# node-mcu-pack-single-sided.net
KiCad netlist of a schematic drawn in EAGLE
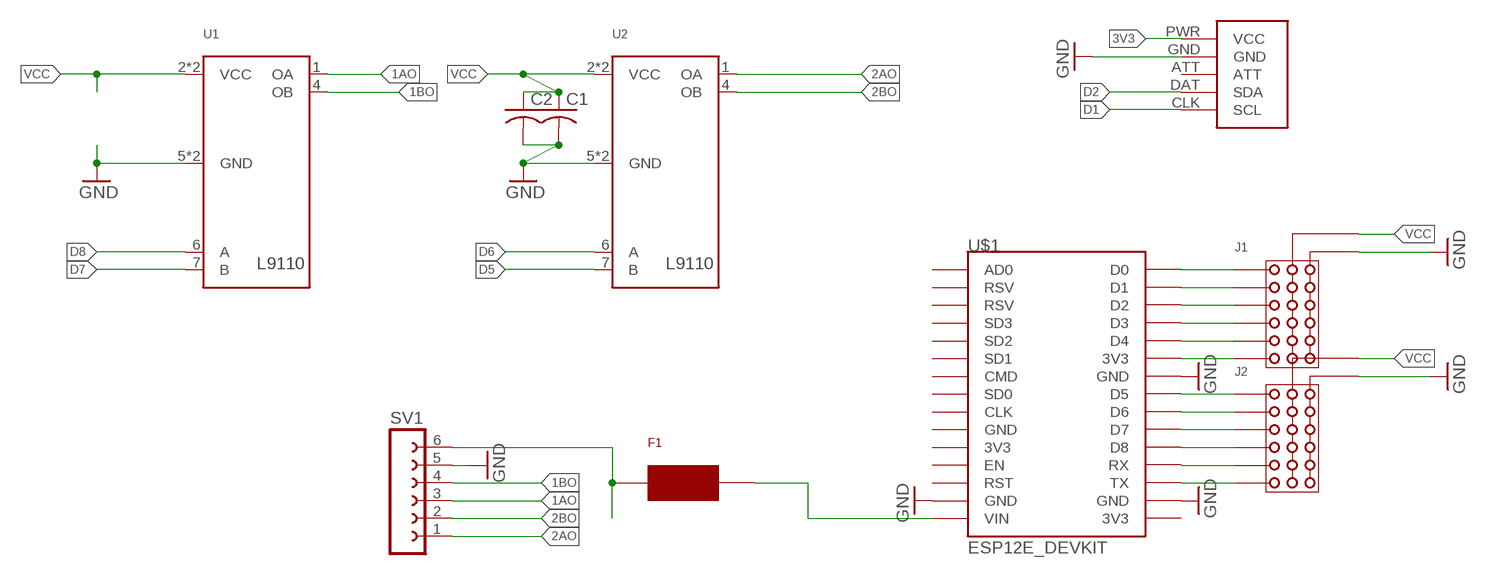
[diagram p0: schematic, sheet 1]

(export (version "E")
  (design (tool "Eeschema 10.0.6"))
  (components
    (comp (ref "C1")
      (value "C-USC0805")
      (footprint "eagle-import:C0805")
      (libsource (lib "eagle-import") (part "C-USC0805"))
    )
    (comp (ref "C2")
      (value "C-USC0805")
      (footprint "eagle-import:C0805")
      (libsource (lib "eagle-import") (part "C-USC0805"))
    )
    (comp (ref "F1")
      (value "0154")
      (footprint "eagle-import:0154")
      (libsource (lib "eagle-import") (part "0154"))
    )
    (comp (ref "J1")
      (value "IOBLOCK6")
      (footprint "eagle-import:IOBLOCK100MILX6")
      (libsource (lib "eagle-import") (part "IOBLOCK6"))
    )
    (comp (ref "J2")
      (value "IOBLOCK6")
      (footprint "eagle-import:IOBLOCK100MILX6")
      (libsource (lib "eagle-import") (part "IOBLOCK6"))
    )
    (comp (ref "SV1")
      (value "FE06-1")
      (footprint "eagle-import:FE06")
      (libsource (lib "eagle-import") (part "FE06-1"))
    )
    (comp (ref "U$1")
      (value "ESP12E_DEVKIT")
      (footprint "eagle-import:ESP12E_DEVKIT")
      (libsource (lib "eagle-import") (part "ESP12E_DEVKIT"))
    )
    (comp (ref "U$2")
      (value "WIICHUCKOUTIE")
      (footprint "eagle-import:CHUCK-OUTIE")
      (libsource (lib "eagle-import") (part "WIICHUCKOUTIE"))
    )
    (comp (ref "U1")
      (value "L9110SMT")
      (footprint "eagle-import:8S1")
      (libsource (lib "eagle-import") (part "L9110SMT"))
    )
    (comp (ref "U2")
      (value "L9110SMT")
      (footprint "eagle-import:8S1")
      (libsource (lib "eagle-import") (part "L9110SMT"))
    )
  )
  (nets
    (net (code "1") (name "1AO") (class "Default")
      (node (ref "SV1") (pin "3") (pinfunction "3_3") (pintype "passive"))
      (node (ref "U1") (pin "1") (pinfunction "OA_1") (pintype "bidirectional"))
    )
    (net (code "2") (name "1BO") (class "Default")
      (node (ref "SV1") (pin "4") (pinfunction "4_4") (pintype "passive"))
      (node (ref "U1") (pin "4") (pinfunction "OB_4") (pintype "bidirectional"))
    )
    (net (code "3") (name "2AO") (class "Default")
      (node (ref "SV1") (pin "1") (pinfunction "1_1") (pintype "passive"))
      (node (ref "U2") (pin "1") (pinfunction "OA_1") (pintype "bidirectional"))
    )
    (net (code "4") (name "2BO") (class "Default")
      (node (ref "SV1") (pin "2") (pinfunction "2_2") (pintype "passive"))
      (node (ref "U2") (pin "4") (pinfunction "OB_4") (pintype "bidirectional"))
    )
    (net (code "5") (name "3V3") (class "Default")
      (node (ref "J1") (pin "P$6") (pinfunction "P$6_P$6") (pintype "bidirectional"))
      (node (ref "U$1") (pin "3V3@1") (pinfunction "3V3_3V3@1") (pintype "bidirectional"))
      (node (ref "U$2") (pin "PWR") (pinfunction "VCC_PWR") (pintype "bidirectional"))
    )
    (net (code "6") (name "D1") (class "Default")
      (node (ref "J1") (pin "P$2") (pinfunction "P$2_P$2") (pintype "bidirectional"))
      (node (ref "U$1") (pin "D1") (pinfunction "D1_D1") (pintype "bidirectional"))
      (node (ref "U$2") (pin "CLK") (pinfunction "SCL_CLK") (pintype "bidirectional"))
    )
    (net (code "7") (name "D2") (class "Default")
      (node (ref "J1") (pin "P$3") (pinfunction "P$3_P$3") (pintype "bidirectional"))
      (node (ref "U$1") (pin "D2") (pinfunction "D2_D2") (pintype "bidirectional"))
      (node (ref "U$2") (pin "DAT") (pinfunction "SDA_DAT") (pintype "bidirectional"))
    )
    (net (code "8") (name "D5") (class "Default")
      (node (ref "J2") (pin "P$1") (pinfunction "P$1_P$1") (pintype "bidirectional"))
      (node (ref "U$1") (pin "D5") (pinfunction "D5_D5") (pintype "bidirectional"))
      (node (ref "U2") (pin "7") (pinfunction "B_7") (pintype "bidirectional"))
    )
    (net (code "9") (name "D6") (class "Default")
      (node (ref "J2") (pin "P$2") (pinfunction "P$2_P$2") (pintype "bidirectional"))
      (node (ref "U$1") (pin "D6") (pinfunction "D6_D6") (pintype "bidirectional"))
      (node (ref "U2") (pin "6") (pinfunction "A_6") (pintype "bidirectional"))
    )
    (net (code "10") (name "D7") (class "Default")
      (node (ref "J2") (pin "P$3") (pinfunction "P$3_P$3") (pintype "bidirectional"))
      (node (ref "U$1") (pin "D7") (pinfunction "D7_D7") (pintype "bidirectional"))
      (node (ref "U1") (pin "7") (pinfunction "B_7") (pintype "bidirectional"))
    )
    (net (code "11") (name "D8") (class "Default")
      (node (ref "J2") (pin "P$4") (pinfunction "P$4_P$4") (pintype "bidirectional"))
      (node (ref "U$1") (pin "D8") (pinfunction "D8_D8") (pintype "bidirectional"))
      (node (ref "U1") (pin "6") (pinfunction "A_6") (pintype "bidirectional"))
    )
    (net (code "12") (name "GND") (class "Default")
      (node (ref "C1") (pin "2") (pinfunction "2_2") (pintype "passive"))
      (node (ref "C2") (pin "2") (pinfunction "2_2") (pintype "passive"))
      (node (ref "J1") (pin "G1") (pinfunction "P$8_G1") (pintype "bidirectional"))
      (node (ref "J1") (pin "G2") (pinfunction "P$8_G2") (pintype "bidirectional"))
      (node (ref "J1") (pin "G3") (pinfunction "P$8_G3") (pintype "bidirectional"))
      (node (ref "J1") (pin "G4") (pinfunction "P$8_G4") (pintype "bidirectional"))
      (node (ref "J1") (pin "G5") (pinfunction "P$8_G5") (pintype "bidirectional"))
      (node (ref "J1") (pin "G6") (pinfunction "P$8_G6") (pintype "bidirectional"))
      (node (ref "J2") (pin "G1") (pinfunction "P$8_G1") (pintype "bidirectional"))
      (node (ref "J2") (pin "G2") (pinfunction "P$8_G2") (pintype "bidirectional"))
      (node (ref "J2") (pin "G3") (pinfunction "P$8_G3") (pintype "bidirectional"))
      (node (ref "J2") (pin "G4") (pinfunction "P$8_G4") (pintype "bidirectional"))
      (node (ref "J2") (pin "G5") (pinfunction "P$8_G5") (pintype "bidirectional"))
      (node (ref "J2") (pin "G6") (pinfunction "P$8_G6") (pintype "bidirectional"))
      (node (ref "SV1") (pin "5") (pinfunction "5_5") (pintype "passive"))
      (node (ref "U$1") (pin "GND@1") (pinfunction "GND_GND@1") (pintype "bidirectional"))
      (node (ref "U$1") (pin "GND@2") (pinfunction "GND_GND@2") (pintype "bidirectional"))
      (node (ref "U$1") (pin "GND@3") (pinfunction "GND_GND@3") (pintype "bidirectional"))
      (node (ref "U$2") (pin "GND") (pinfunction "GND_GND") (pintype "bidirectional"))
      (node (ref "U1") (pin "5") (pinfunction "GND_5") (pintype "bidirectional"))
      (node (ref "U1") (pin "8") (pinfunction "GND_8") (pintype "bidirectional"))
      (node (ref "U2") (pin "5") (pinfunction "GND_5") (pintype "bidirectional"))
      (node (ref "U2") (pin "8") (pinfunction "GND_8") (pintype "bidirectional"))
    )
    (net (code "13") (name "Net-(F1-P$1)") (class "Default")
      (node (ref "F1") (pin "1") (pinfunction "P$1_1") (pintype "bidirectional"))
      (node (ref "SV1") (pin "6") (pinfunction "6_6") (pintype "passive"))
    )
    (net (code "14") (name "Net-(J1-PadP$1)") (class "Default")
      (node (ref "J1") (pin "P$1") (pinfunction "P$1_P$1") (pintype "bidirectional"))
      (node (ref "U$1") (pin "D0") (pinfunction "D0_D0") (pintype "bidirectional"))
    )
    (net (code "15") (name "Net-(J1-PadP$4)") (class "Default")
      (node (ref "J1") (pin "P$4") (pinfunction "P$4_P$4") (pintype "bidirectional"))
      (node (ref "U$1") (pin "D3") (pinfunction "D3_D3") (pintype "bidirectional"))
    )
    (net (code "16") (name "Net-(J1-PadP$5)") (class "Default")
      (node (ref "J1") (pin "P$5") (pinfunction "P$5_P$5") (pintype "bidirectional"))
      (node (ref "U$1") (pin "D4") (pinfunction "D4_D4") (pintype "bidirectional"))
    )
    (net (code "17") (name "Net-(J2-PadP$5)") (class "Default")
      (node (ref "J2") (pin "P$5") (pinfunction "P$5_P$5") (pintype "bidirectional"))
      (node (ref "U$1") (pin "RX") (pinfunction "RX_RX") (pintype "bidirectional"))
    )
    (net (code "18") (name "Net-(J2-PadP$6)") (class "Default")
      (node (ref "J2") (pin "P$6") (pinfunction "P$6_P$6") (pintype "bidirectional"))
      (node (ref "U$1") (pin "TX") (pinfunction "TX_TX") (pintype "bidirectional"))
    )
    (net (code "19") (name "VCC") (class "Default")
      (node (ref "C1") (pin "1") (pinfunction "1_1") (pintype "passive"))
      (node (ref "C2") (pin "1") (pinfunction "1_1") (pintype "passive"))
      (node (ref "F1") (pin "2") (pinfunction "P$2_2") (pintype "bidirectional"))
      (node (ref "J1") (pin "P1") (pinfunction "P$7_P1") (pintype "bidirectional"))
      (node (ref "J1") (pin "P2") (pinfunction "P$7_P2") (pintype "bidirectional"))
      (node (ref "J1") (pin "P3") (pinfunction "P$7_P3") (pintype "bidirectional"))
      (node (ref "J1") (pin "P4") (pinfunction "P$7_P4") (pintype "bidirectional"))
      (node (ref "J1") (pin "P5") (pinfunction "P$7_P5") (pintype "bidirectional"))
      (node (ref "J1") (pin "P6") (pinfunction "P$7_P6") (pintype "bidirectional"))
      (node (ref "J2") (pin "P1") (pinfunction "P$7_P1") (pintype "bidirectional"))
      (node (ref "J2") (pin "P2") (pinfunction "P$7_P2") (pintype "bidirectional"))
      (node (ref "J2") (pin "P3") (pinfunction "P$7_P3") (pintype "bidirectional"))
      (node (ref "J2") (pin "P4") (pinfunction "P$7_P4") (pintype "bidirectional"))
      (node (ref "J2") (pin "P5") (pinfunction "P$7_P5") (pintype "bidirectional"))
      (node (ref "J2") (pin "P6") (pinfunction "P$7_P6") (pintype "bidirectional"))
      (node (ref "U$1") (pin "VIN") (pinfunction "VIN_VIN") (pintype "bidirectional"))
      (node (ref "U1") (pin "2") (pinfunction "VCC_2") (pintype "bidirectional"))
      (node (ref "U1") (pin "3") (pinfunction "VCC_3") (pintype "bidirectional"))
      (node (ref "U2") (pin "2") (pinfunction "VCC_2") (pintype "bidirectional"))
      (node (ref "U2") (pin "3") (pinfunction "VCC_3") (pintype "bidirectional"))
    )
    (net (code "20") (name "unconnected-(U$1-3V3-Pad3V3@0)") (class "Default")
      (node (ref "U$1") (pin "3V3@0") (pinfunction "3V3_3V3@0") (pintype "bidirectional"))
    )
    (net (code "21") (name "unconnected-(U$1-3V3-Pad3V3@2)") (class "Default")
      (node (ref "U$1") (pin "3V3@2") (pinfunction "3V3_3V3@2") (pintype "bidirectional"))
    )
    (net (code "22") (name "unconnected-(U$1-GND-PadGND@0)") (class "Default")
      (node (ref "U$1") (pin "GND@0") (pinfunction "GND_GND@0") (pintype "bidirectional"))
    )
    (net (code "23") (name "unconnected-(U$1-PadAD0)") (class "Default")
      (node (ref "U$1") (pin "AD0") (pinfunction "AD0_AD0") (pintype "bidirectional"))
    )
    (net (code "24") (name "unconnected-(U$1-PadCLK)") (class "Default")
      (node (ref "U$1") (pin "CLK") (pinfunction "CLK_CLK") (pintype "bidirectional"))
    )
    (net (code "25") (name "unconnected-(U$1-PadCMD)") (class "Default")
      (node (ref "U$1") (pin "CMD") (pinfunction "CMD_CMD") (pintype "bidirectional"))
    )
    (net (code "26") (name "unconnected-(U$1-PadEN)") (class "Default")
      (node (ref "U$1") (pin "EN") (pinfunction "EN_EN") (pintype "bidirectional"))
    )
    (net (code "27") (name "unconnected-(U$1-PadRST)") (class "Default")
      (node (ref "U$1") (pin "RST") (pinfunction "RST_RST") (pintype "bidirectional"))
    )
    (net (code "28") (name "unconnected-(U$1-PadSD0)") (class "Default")
      (node (ref "U$1") (pin "SD0") (pinfunction "SD0_SD0") (pintype "bidirectional"))
    )
    (net (code "29") (name "unconnected-(U$1-PadSD1)") (class "Default")
      (node (ref "U$1") (pin "SD1") (pinfunction "SD1_SD1") (pintype "bidirectional"))
    )
    (net (code "30") (name "unconnected-(U$1-PadSD2)") (class "Default")
      (node (ref "U$1") (pin "SD2") (pinfunction "SD2_SD2") (pintype "bidirectional"))
    )
    (net (code "31") (name "unconnected-(U$1-PadSD3)") (class "Default")
      (node (ref "U$1") (pin "SD3") (pinfunction "SD3_SD3") (pintype "bidirectional"))
    )
    (net (code "32") (name "unconnected-(U$1-RSV-PadRSV@0)") (class "Default")
      (node (ref "U$1") (pin "RSV@0") (pinfunction "RSV_RSV@0") (pintype "bidirectional"))
    )
    (net (code "33") (name "unconnected-(U$1-RSV-PadRSV@1)") (class "Default")
      (node (ref "U$1") (pin "RSV@1") (pinfunction "RSV_RSV@1") (pintype "bidirectional"))
    )
    (net (code "34") (name "unconnected-(U$2-PadATT)") (class "Default")
      (node (ref "U$2") (pin "ATT") (pinfunction "ATT_ATT") (pintype "bidirectional"))
    )
  )
)
